# B_Main_board_v1_4.net
KiCad netlist of a schematic drawn in EAGLE
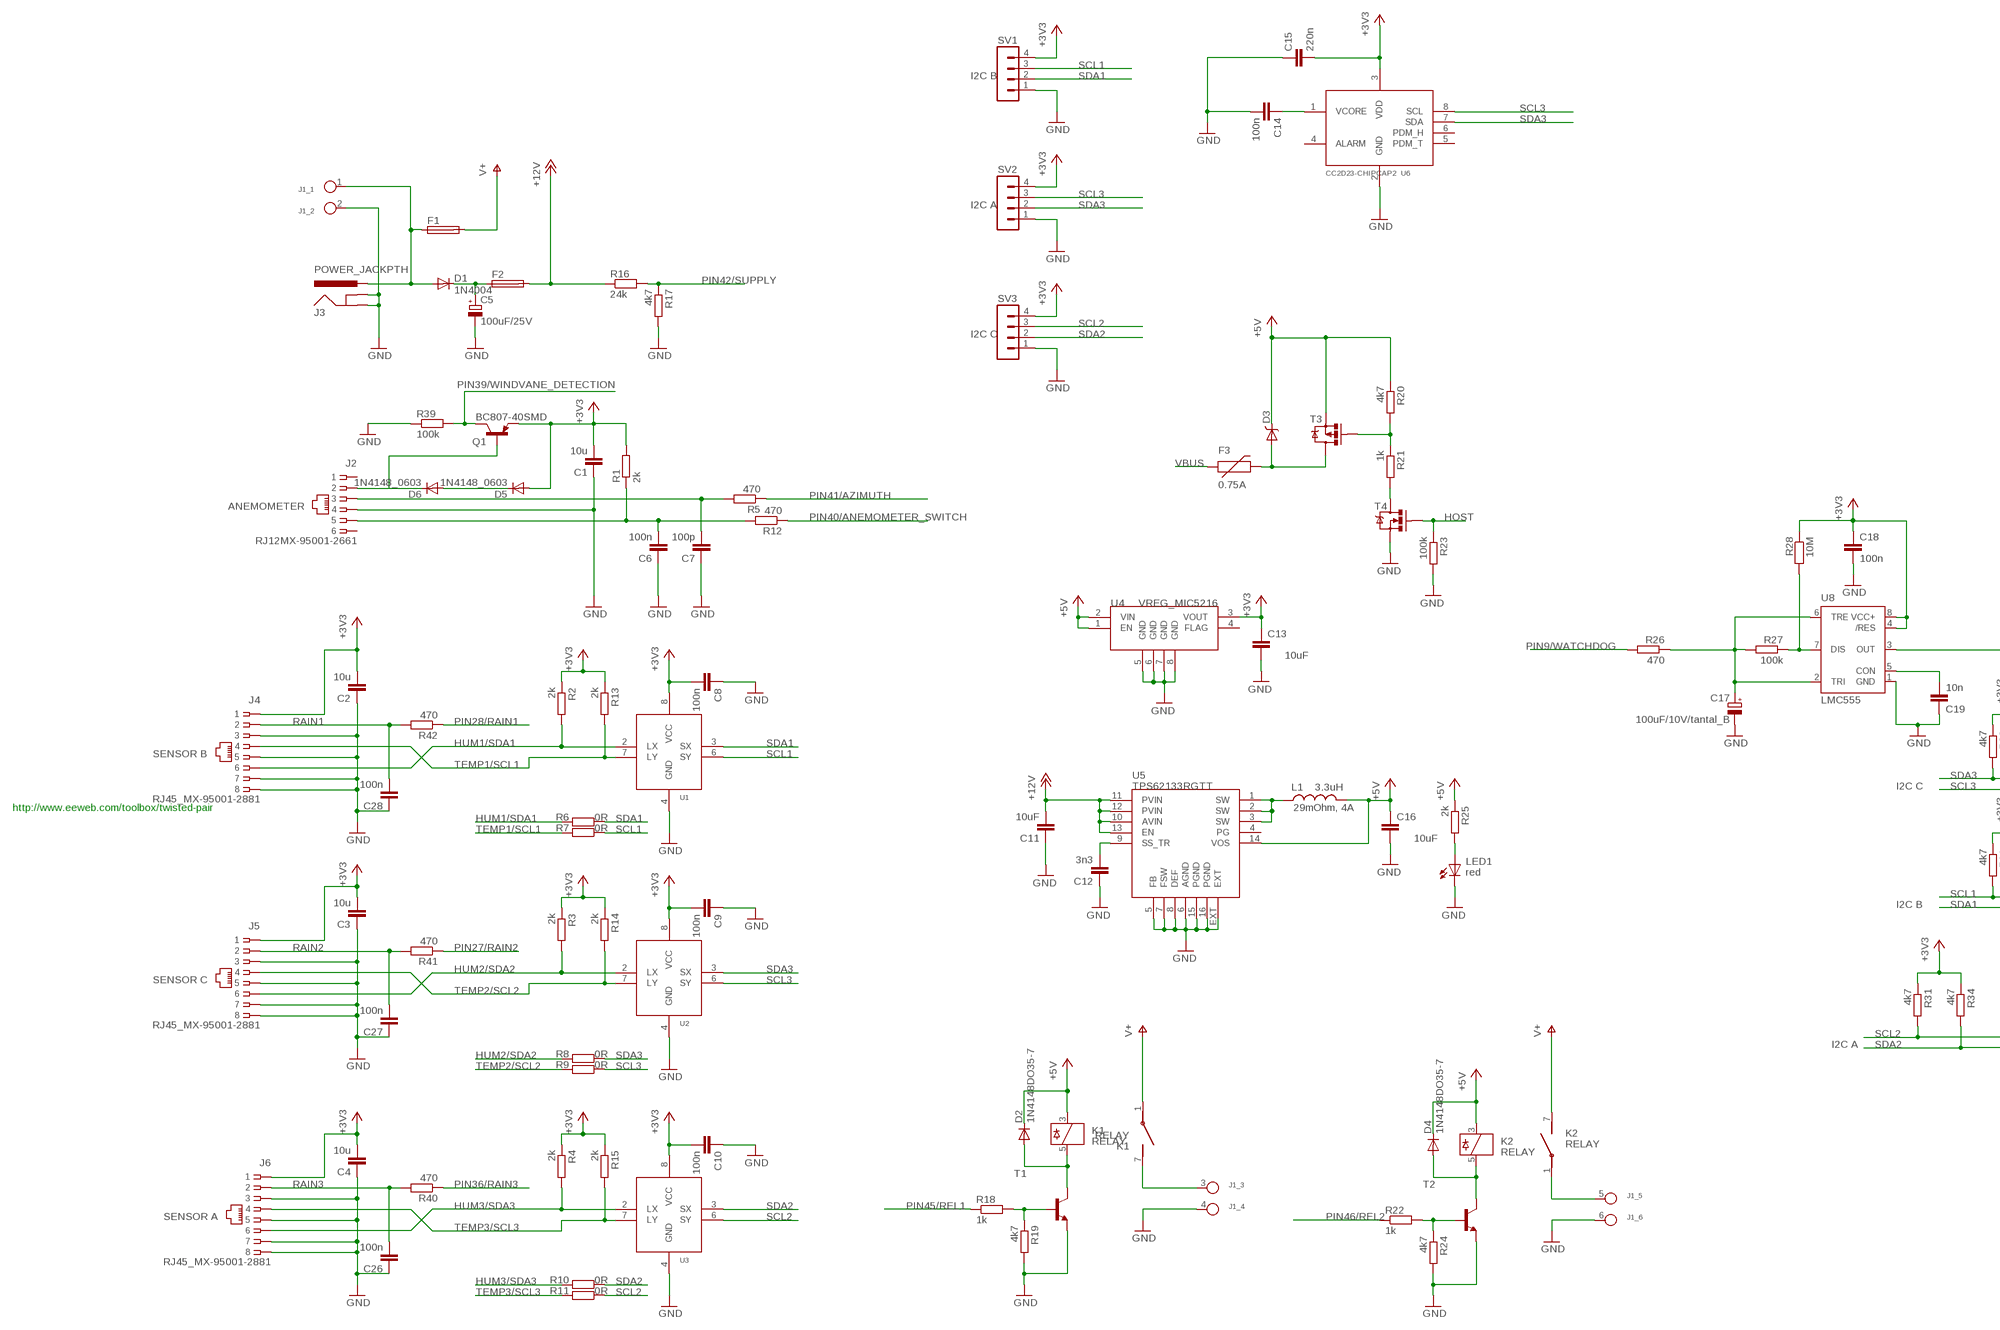
[diagram p0: schematic, sheet 1, part 1 of 2]
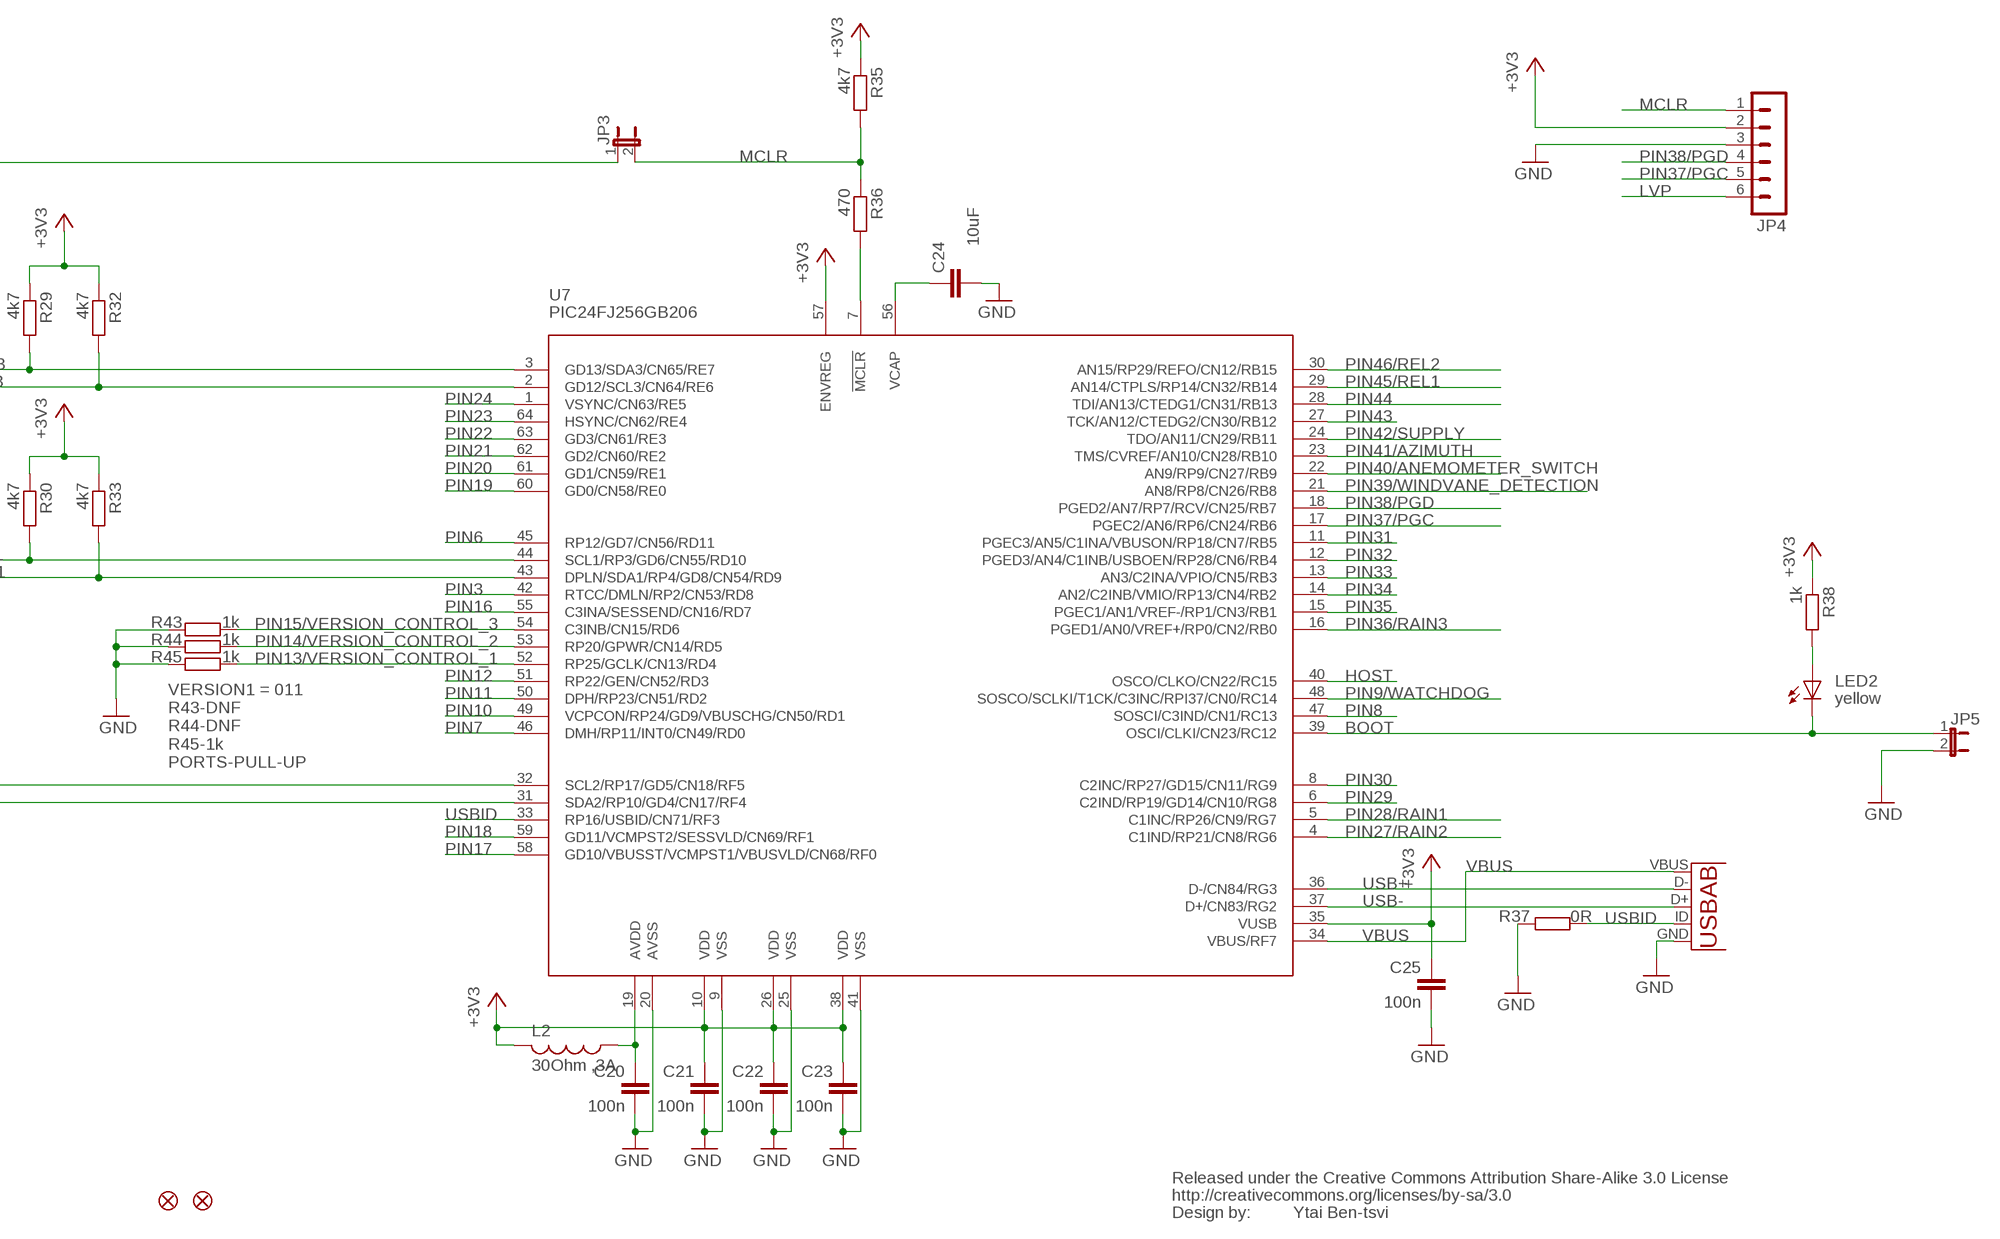
[diagram p1: schematic, sheet 1, part 2 of 2]

(export (version "E")
  (design (tool "Eeschema 10.0.6"))
  (components
    (comp (ref "C1")
      (value "10u")
      (footprint "eagle-import:C1206")
      (libsource (lib "eagle-import") (part "C-EUC1206"))
    )
    (comp (ref "C2")
      (value "10u")
      (footprint "eagle-import:C1206")
      (libsource (lib "eagle-import") (part "C-EUC1206"))
    )
    (comp (ref "C3")
      (value "10u")
      (footprint "eagle-import:C1206")
      (libsource (lib "eagle-import") (part "C-EUC1206"))
    )
    (comp (ref "C4")
      (value "10u")
      (footprint "eagle-import:C1206")
      (libsource (lib "eagle-import") (part "C-EUC1206"))
    )
    (comp (ref "C5")
      (value "100uF/25V")
      (footprint "eagle-import:E2-5")
      (libsource (lib "eagle-import") (part "CPOL-EUE2-5"))
    )
    (comp (ref "C6")
      (value "100n")
      (footprint "eagle-import:C1206")
      (libsource (lib "eagle-import") (part "C-EUC1206"))
    )
    (comp (ref "C7")
      (value "100p")
      (footprint "eagle-import:C1206")
      (libsource (lib "eagle-import") (part "C-EUC1206"))
    )
    (comp (ref "C8")
      (value "100n")
      (footprint "eagle-import:C1206")
      (libsource (lib "eagle-import") (part "C-EUC1206"))
    )
    (comp (ref "C9")
      (value "100n")
      (footprint "eagle-import:C1206")
      (libsource (lib "eagle-import") (part "C-EUC1206"))
    )
    (comp (ref "C10")
      (value "100n")
      (footprint "eagle-import:C1206")
      (libsource (lib "eagle-import") (part "C-EUC1206"))
    )
    (comp (ref "C11")
      (value "10uF")
      (footprint "eagle-import:C1206")
      (libsource (lib "eagle-import") (part "C-EUC1206"))
    )
    (comp (ref "C12")
      (value "3n3")
      (footprint "eagle-import:C1206")
      (libsource (lib "eagle-import") (part "C-EUC1206"))
    )
    (comp (ref "C13")
      (value "10uF")
      (footprint "eagle-import:C1206")
      (libsource (lib "eagle-import") (part "C-EUC1206"))
    )
    (comp (ref "C14")
      (value "100n")
      (footprint "eagle-import:C1206")
      (libsource (lib "eagle-import") (part "C-EUC1206"))
    )
    (comp (ref "C15")
      (value "220n")
      (footprint "eagle-import:C1206")
      (libsource (lib "eagle-import") (part "C-EUC1206"))
    )
    (comp (ref "C16")
      (value "10uF")
      (footprint "eagle-import:C1206")
      (libsource (lib "eagle-import") (part "C-EUC1206"))
    )
    (comp (ref "C17")
      (value "100uF/10V/tantal_B")
      (footprint "eagle-import:B_3528-21R")
      (libsource (lib "eagle-import") (part "rcl_CPOL-EUB/3528-21R"))
    )
    (comp (ref "C18")
      (value "100n")
      (footprint "eagle-import:C1206")
      (libsource (lib "eagle-import") (part "C-EUC1206"))
    )
    (comp (ref "C19")
      (value "10n")
      (footprint "eagle-import:C1206")
      (libsource (lib "eagle-import") (part "C-EUC1206"))
    )
    (comp (ref "C20")
      (value "100n")
      (footprint "eagle-import:C1206")
      (libsource (lib "eagle-import") (part "C-EUC1206"))
    )
    (comp (ref "C21")
      (value "100n")
      (footprint "eagle-import:C1206")
      (libsource (lib "eagle-import") (part "C-EUC1206"))
    )
    (comp (ref "C22")
      (value "100n")
      (footprint "eagle-import:C1206")
      (libsource (lib "eagle-import") (part "C-EUC1206"))
    )
    (comp (ref "C23")
      (value "100n")
      (footprint "eagle-import:C1206")
      (libsource (lib "eagle-import") (part "C-EUC1206"))
    )
    (comp (ref "C24")
      (value "10uF")
      (footprint "eagle-import:C1206")
      (libsource (lib "eagle-import") (part "C-EUC1206"))
    )
    (comp (ref "C25")
      (value "100n")
      (footprint "eagle-import:C1206")
      (libsource (lib "eagle-import") (part "C-EUC1206"))
    )
    (comp (ref "C26")
      (value "100n")
      (footprint "eagle-import:C1206")
      (libsource (lib "eagle-import") (part "C-EUC1206"))
    )
    (comp (ref "C27")
      (value "100n")
      (footprint "eagle-import:C1206")
      (libsource (lib "eagle-import") (part "C-EUC1206"))
    )
    (comp (ref "C28")
      (value "100n")
      (footprint "eagle-import:C1206")
      (libsource (lib "eagle-import") (part "C-EUC1206"))
    )
    (comp (ref "D1")
      (value "1N4004")
      (footprint "eagle-import:DO41-10")
      (libsource (lib "eagle-import") (part "1N4004"))
    )
    (comp (ref "D2")
      (value "1N4148DO35-7")
      (footprint "eagle-import:DO35-7")
      (libsource (lib "eagle-import") (part "1N4148DO35-7"))
    )
    (comp (ref "D3")
      (value "B340A")
      (footprint "eagle-import:SMA-DIODE")
      (fields (field (name "PART#") "B340A"))
      (libsource (lib "eagle-import") (part "DIODE-SCHOTTKY_"))
    )
    (comp (ref "D4")
      (value "1N4148DO35-7")
      (footprint "eagle-import:DO35-7")
      (libsource (lib "eagle-import") (part "1N4148DO35-7"))
    )
    (comp (ref "D5")
      (value "1N4148_0603")
      (footprint "eagle-import:D0603")
      (libsource (lib "eagle-import") (part "1N4148_0603"))
    )
    (comp (ref "D6")
      (value "1N4148_0603")
      (footprint "eagle-import:D0603")
      (libsource (lib "eagle-import") (part "1N4148_0603"))
    )
    (comp (ref "F1")
      (value "FUSE_HOLDER")
      (footprint "eagle-import:ZHL30")
      (libsource (lib "eagle-import") (part "FUSE_HOLDER"))
    )
    (comp (ref "F2")
      (value "FUSE_HOLDER")
      (footprint "eagle-import:ZHL30")
      (libsource (lib "eagle-import") (part "FUSE_HOLDER"))
    )
    (comp (ref "F3")
      (value "PTCSMD")
      (footprint "eagle-import:PTC-1206")
      (fields (field (name "PART#") "0ZCA0075FF2G"))
      (libsource (lib "eagle-import") (part "PTCSMD"))
    )
    (comp (ref "J1")
      (value "6P_CONN")
      (footprint "eagle-import:MOLEX_39543-0006")
      (libsource (lib "eagle-import") (part "6P_CONN"))
    )
    (comp (ref "J2")
      (value "RJ12MX-95001-2661")
      (footprint "eagle-import:MX-95001-2661")
      (libsource (lib "eagle-import") (part "RJ12MX-95001-2661"))
    )
    (comp (ref "J3")
      (value "POWER_JACKPTH")
      (footprint "eagle-import:PC-GK2.1")
      (libsource (lib "eagle-import") (part "POWER_JACKPTH"))
    )
    (comp (ref "J4")
      (value "RJ45_MX-95001-2881")
      (footprint "eagle-import:MX-95001-2881")
      (libsource (lib "eagle-import") (part "RJ45_MX-95001-2881"))
    )
    (comp (ref "J5")
      (value "RJ45_MX-95001-2881")
      (footprint "eagle-import:MX-95001-2881")
      (libsource (lib "eagle-import") (part "RJ45_MX-95001-2881"))
    )
    (comp (ref "J6")
      (value "RJ45_MX-95001-2881")
      (footprint "eagle-import:MX-95001-2881")
      (libsource (lib "eagle-import") (part "RJ45_MX-95001-2881"))
    )
    (comp (ref "J7")
      (value "10104111-0001LF")
      (footprint "eagle-import:USB-AB-MICRO-SMD")
      (libsource (lib "eagle-import") (part "USB_AB"))
    )
    (comp (ref "JP1")
      (value "FIDUCIALUFIDUCIAL")
      (footprint "eagle-import:MICRO-FIDUCIAL")
      (libsource (lib "eagle-import") (part "FIDUCIALUFIDUCIAL"))
    )
    (comp (ref "JP2")
      (value "FIDUCIALUFIDUCIAL")
      (footprint "eagle-import:MICRO-FIDUCIAL")
      (libsource (lib "eagle-import") (part "FIDUCIALUFIDUCIAL"))
    )
    (comp (ref "JP3")
      (value "JUMPER-2PTH")
      (footprint "eagle-import:1X02")
      (libsource (lib "eagle-import") (part "JUMPER-2PTH"))
    )
    (comp (ref "JP4")
      (value "MA06-1")
      (footprint "eagle-import:MA06-1")
      (libsource (lib "eagle-import") (part "MA06-1"))
    )
    (comp (ref "JP5")
      (value "JUMPER-2PTH")
      (footprint "eagle-import:1X02")
      (libsource (lib "eagle-import") (part "JUMPER-2PTH"))
    )
    (comp (ref "K1")
      (value "RELAY")
      (footprint "eagle-import:JV-5S-KT")
      (libsource (lib "eagle-import") (part "RELAY"))
    )
    (comp (ref "K2")
      (value "RELAY")
      (footprint "eagle-import:JV-5S-KT")
      (libsource (lib "eagle-import") (part "RELAY"))
    )
    (comp (ref "L1")
      (value "VLC5045T-3R3N")
      (footprint "eagle-import:CR54")
      (fields (field (name "AM") "3.3uH"))
      (libsource (lib "eagle-import") (part "INDUCTORCR54"))
    )
    (comp (ref "L2")
      (value "30Ohm ,3A")
      (footprint "eagle-import:R1206")
      (libsource (lib "eagle-import") (part "L-US"))
    )
    (comp (ref "LED1")
      (value "LS L29K-G1J2-1-Z")
      (footprint "eagle-import:LED-1206")
      (libsource (lib "eagle-import") (part "LED1206"))
    )
    (comp (ref "LED2")
      (value "LY L29K-J1K2-26-Z")
      (footprint "eagle-import:LED-1206")
      (libsource (lib "eagle-import") (part "LED1206"))
    )
    (comp (ref "Q1")
      (value "BC807-40SMD")
      (footprint "eagle-import:SOT23-BEC")
      (libsource (lib "eagle-import") (part "BC807SMD-40"))
    )
    (comp (ref "R1")
      (value "2k")
      (footprint "eagle-import:R1206")
      (libsource (lib "eagle-import") (part "R-EU_R1206"))
    )
    (comp (ref "R2")
      (value "2k")
      (footprint "eagle-import:R1206")
      (libsource (lib "eagle-import") (part "R-EU_R1206"))
    )
    (comp (ref "R3")
      (value "2k")
      (footprint "eagle-import:R1206")
      (libsource (lib "eagle-import") (part "R-EU_R1206"))
    )
    (comp (ref "R4")
      (value "2k")
      (footprint "eagle-import:R1206")
      (libsource (lib "eagle-import") (part "R-EU_R1206"))
    )
    (comp (ref "R5")
      (value "470")
      (footprint "eagle-import:R1206")
      (libsource (lib "eagle-import") (part "R-EU_R1206"))
    )
    (comp (ref "R6")
      (value "0R")
      (footprint "eagle-import:R1206")
      (libsource (lib "eagle-import") (part "R-EU_R1206"))
    )
    (comp (ref "R7")
      (value "0R")
      (footprint "eagle-import:R1206")
      (libsource (lib "eagle-import") (part "R-EU_R1206"))
    )
    (comp (ref "R8")
      (value "0R")
      (footprint "eagle-import:R1206")
      (libsource (lib "eagle-import") (part "R-EU_R1206"))
    )
    (comp (ref "R9")
      (value "0R")
      (footprint "eagle-import:R1206")
      (libsource (lib "eagle-import") (part "R-EU_R1206"))
    )
    (comp (ref "R10")
      (value "0R")
      (footprint "eagle-import:R1206")
      (libsource (lib "eagle-import") (part "R-EU_R1206"))
    )
    (comp (ref "R11")
      (value "0R")
      (footprint "eagle-import:R1206")
      (libsource (lib "eagle-import") (part "R-EU_R1206"))
    )
    (comp (ref "R12")
      (value "470")
      (footprint "eagle-import:R1206")
      (libsource (lib "eagle-import") (part "R-EU_R1206"))
    )
    (comp (ref "R13")
      (value "2k")
      (footprint "eagle-import:R1206")
      (libsource (lib "eagle-import") (part "R-EU_R1206"))
    )
    (comp (ref "R14")
      (value "2k")
      (footprint "eagle-import:R1206")
      (libsource (lib "eagle-import") (part "R-EU_R1206"))
    )
    (comp (ref "R15")
      (value "2k")
      (footprint "eagle-import:R1206")
      (libsource (lib "eagle-import") (part "R-EU_R1206"))
    )
    (comp (ref "R16")
      (value "24k")
      (footprint "eagle-import:R1206")
      (libsource (lib "eagle-import") (part "R-EU_R1206"))
    )
    (comp (ref "R17")
      (value "4k7")
      (footprint "eagle-import:R1206")
      (libsource (lib "eagle-import") (part "R-EU_R1206"))
    )
    (comp (ref "R18")
      (value "1k")
      (footprint "eagle-import:R1206")
      (libsource (lib "eagle-import") (part "R-EU_R1206"))
    )
    (comp (ref "R19")
      (value "4k7")
      (footprint "eagle-import:R1206")
      (libsource (lib "eagle-import") (part "R-EU_R1206"))
    )
    (comp (ref "R20")
      (value "4k7")
      (footprint "eagle-import:R1206")
      (libsource (lib "eagle-import") (part "R-EU_R1206"))
    )
    (comp (ref "R21")
      (value "1k")
      (footprint "eagle-import:R1206")
      (libsource (lib "eagle-import") (part "R-EU_R1206"))
    )
    (comp (ref "R22")
      (value "1k")
      (footprint "eagle-import:R1206")
      (libsource (lib "eagle-import") (part "R-EU_R1206"))
    )
    (comp (ref "R23")
      (value "100k")
      (footprint "eagle-import:R1206")
      (libsource (lib "eagle-import") (part "R-EU_R1206"))
    )
    (comp (ref "R24")
      (value "4k7")
      (footprint "eagle-import:R1206")
      (libsource (lib "eagle-import") (part "R-EU_R1206"))
    )
    (comp (ref "R25")
      (value "2k")
      (footprint "eagle-import:R1206")
      (libsource (lib "eagle-import") (part "R-EU_R1206"))
    )
    (comp (ref "R26")
      (value "470")
      (footprint "eagle-import:R1206")
      (libsource (lib "eagle-import") (part "R-EU_R1206"))
    )
    (comp (ref "R27")
      (value "100k")
      (footprint "eagle-import:R1206")
      (libsource (lib "eagle-import") (part "R-EU_R1206"))
    )
    (comp (ref "R28")
      (value "10M")
      (footprint "eagle-import:R1206")
      (libsource (lib "eagle-import") (part "R-EU_R1206"))
    )
    (comp (ref "R29")
      (value "4k7")
      (footprint "eagle-import:R1206")
      (libsource (lib "eagle-import") (part "R-EU_R1206"))
    )
    (comp (ref "R30")
      (value "4k7")
      (footprint "eagle-import:R1206")
      (libsource (lib "eagle-import") (part "R-EU_R1206"))
    )
    (comp (ref "R31")
      (value "4k7")
      (footprint "eagle-import:R1206")
      (libsource (lib "eagle-import") (part "R-EU_R1206"))
    )
    (comp (ref "R32")
      (value "4k7")
      (footprint "eagle-import:R1206")
      (libsource (lib "eagle-import") (part "R-EU_R1206"))
    )
    (comp (ref "R33")
      (value "4k7")
      (footprint "eagle-import:R1206")
      (libsource (lib "eagle-import") (part "R-EU_R1206"))
    )
    (comp (ref "R34")
      (value "4k7")
      (footprint "eagle-import:R1206")
      (libsource (lib "eagle-import") (part "R-EU_R1206"))
    )
    (comp (ref "R35")
      (value "4k7")
      (footprint "eagle-import:R1206")
      (libsource (lib "eagle-import") (part "R-EU_R1206"))
    )
    (comp (ref "R36")
      (value "470")
      (footprint "eagle-import:R1206")
      (libsource (lib "eagle-import") (part "R-EU_R1206"))
    )
    (comp (ref "R37")
      (value "0R")
      (footprint "eagle-import:R1206")
      (libsource (lib "eagle-import") (part "R-EU_R1206"))
    )
    (comp (ref "R38")
      (value "1k")
      (footprint "eagle-import:R1206")
      (libsource (lib "eagle-import") (part "R-EU_R1206"))
    )
    (comp (ref "R39")
      (value "100k")
      (footprint "eagle-import:R1206")
      (libsource (lib "eagle-import") (part "R-EU_R1206"))
    )
    (comp (ref "R40")
      (value "470")
      (footprint "eagle-import:R1206")
      (libsource (lib "eagle-import") (part "R-EU_R1206"))
    )
    (comp (ref "R41")
      (value "470")
      (footprint "eagle-import:R1206")
      (libsource (lib "eagle-import") (part "R-EU_R1206"))
    )
    (comp (ref "R42")
      (value "470")
      (footprint "eagle-import:R1206")
      (libsource (lib "eagle-import") (part "R-EU_R1206"))
    )
    (comp (ref "R43")
      (value "1k")
      (footprint "eagle-import:R1206")
      (libsource (lib "eagle-import") (part "R-EU_R1206"))
    )
    (comp (ref "R44")
      (value "1k")
      (footprint "eagle-import:R1206")
      (libsource (lib "eagle-import") (part "R-EU_R1206"))
    )
    (comp (ref "R45")
      (value "1k")
      (footprint "eagle-import:R1206")
      (libsource (lib "eagle-import") (part "R-EU_R1206"))
    )
    (comp (ref "SV1")
      (value "MA04-1")
      (footprint "eagle-import:MA04-1")
      (libsource (lib "eagle-import") (part "MA04-1"))
    )
    (comp (ref "SV2")
      (value "MA04-1")
      (footprint "eagle-import:MA04-1")
      (libsource (lib "eagle-import") (part "MA04-1"))
    )
    (comp (ref "SV3")
      (value "MA04-1")
      (footprint "eagle-import:MA04-1")
      (libsource (lib "eagle-import") (part "MA04-1"))
    )
    (comp (ref "T1")
      (value "BC817-16-NPN-SOT23-BEC")
      (footprint "eagle-import:SOT23-BEC")
      (libsource (lib "eagle-import") (part "-NPN-SOT23-BECBC817-16"))
    )
    (comp (ref "T2")
      (value "BC817-16-NPN-SOT23-BEC")
      (footprint "eagle-import:SOT23-BEC")
      (libsource (lib "eagle-import") (part "-NPN-SOT23-BECBC817-16"))
    )
    (comp (ref "T3")
      (value "IRLML2244")
      (footprint "eagle-import:SOT23-3")
      (libsource (lib "eagle-import") (part "MOSFET-PCHANNELSMD"))
    )
    (comp (ref "T4")
      (value "2N7002PW")
      (footprint "eagle-import:SOT323")
      (fields (field (name "PART#") "2N7002PW"))
      (libsource (lib "eagle-import") (part "MOSFET-NCHANNELSOT323"))
    )
    (comp (ref "U$1")
      (value "CREATIVE_COMMONS")
      (footprint "eagle-import:CREATIVE_COMMONS")
      (libsource (lib "eagle-import") (part "CREATIVE_COMMONS"))
    )
    (comp (ref "U1")
      (value "P82B715_I2C_BUS_EXTENDER")
      (footprint "eagle-import:SO-08")
      (libsource (lib "eagle-import") (part "P82B715_I2C_BUS_EXTENDER"))
    )
    (comp (ref "U2")
      (value "P82B715_I2C_BUS_EXTENDER")
      (footprint "eagle-import:SO-08")
      (libsource (lib "eagle-import") (part "P82B715_I2C_BUS_EXTENDER"))
    )
    (comp (ref "U3")
      (value "P82B715_I2C_BUS_EXTENDER")
      (footprint "eagle-import:SO-08")
      (libsource (lib "eagle-import") (part "P82B715_I2C_BUS_EXTENDER"))
    )
    (comp (ref "U4")
      (value "VREG_MIC5216")
      (footprint "eagle-import:MSOP8")
      (libsource (lib "eagle-import") (part "VREG_MIC5216"))
    )
    (comp (ref "U5")
      (value "TPS62133RGTT")
      (footprint "eagle-import:QFN16-3X3MM")
      (libsource (lib "eagle-import") (part "TPS6214X"))
    )
    (comp (ref "U6")
      (value "CC2D23-CHIPCAP2")
      (footprint "eagle-import:CC2D23-CHIPCAP2")
      (libsource (lib "eagle-import") (part "CC2D23-CHIPCAP2"))
    )
    (comp (ref "U7")
      (value "PIC24FJ256GB206")
      (footprint "eagle-import:PIC24FXXX_TQFP64")
      (libsource (lib "eagle-import") (part "PIC24FXXXDAX06"))
    )
    (comp (ref "U8")
      (value "LMC555")
      (footprint "eagle-import:SO08")
      (libsource (lib "eagle-import") (part "NE555D"))
    )
  )
  (nets
    (net (code "1") (name "+3V3") (class "Default")
      (node (ref "C1") (pin "2") (pinfunction "2_2") (pintype "passive"))
      (node (ref "C10") (pin "2") (pinfunction "2_2") (pintype "passive"))
      (node (ref "C13") (pin "2") (pinfunction "2_2") (pintype "passive"))
      (node (ref "C15") (pin "2") (pinfunction "2_2") (pintype "passive"))
      (node (ref "C18") (pin "1") (pinfunction "1_1") (pintype "passive"))
      (node (ref "C2") (pin "2") (pinfunction "2_2") (pintype "passive"))
      (node (ref "C21") (pin "1") (pinfunction "1_1") (pintype "passive"))
      (node (ref "C22") (pin "1") (pinfunction "1_1") (pintype "passive"))
      (node (ref "C23") (pin "1") (pinfunction "1_1") (pintype "passive"))
      (node (ref "C25") (pin "1") (pinfunction "1_1") (pintype "passive"))
      (node (ref "C3") (pin "2") (pinfunction "2_2") (pintype "passive"))
      (node (ref "C4") (pin "2") (pinfunction "2_2") (pintype "passive"))
      (node (ref "C8") (pin "2") (pinfunction "2_2") (pintype "passive"))
      (node (ref "C9") (pin "2") (pinfunction "2_2") (pintype "passive"))
      (node (ref "D5") (pin "A") (pinfunction "A_A") (pintype "passive"))
      (node (ref "J4") (pin "1") (pinfunction "1_1") (pintype "passive"))
      (node (ref "J5") (pin "1") (pinfunction "1_1") (pintype "passive"))
      (node (ref "J6") (pin "1") (pinfunction "1_1") (pintype "passive"))
      (node (ref "JP4") (pin "2") (pinfunction "2_2") (pintype "passive"))
      (node (ref "L2") (pin "2") (pinfunction "2_2") (pintype "passive"))
      (node (ref "Q1") (pin "E") (pinfunction "E_E") (pintype "passive"))
      (node (ref "R1") (pin "2") (pinfunction "2_2") (pintype "passive"))
      (node (ref "R13") (pin "1") (pinfunction "1_1") (pintype "passive"))
      (node (ref "R14") (pin "1") (pinfunction "1_1") (pintype "passive"))
      (node (ref "R15") (pin "1") (pinfunction "1_1") (pintype "passive"))
      (node (ref "R2") (pin "1") (pinfunction "1_1") (pintype "passive"))
      (node (ref "R28") (pin "1") (pinfunction "1_1") (pintype "passive"))
      (node (ref "R29") (pin "1") (pinfunction "1_1") (pintype "passive"))
      (node (ref "R3") (pin "1") (pinfunction "1_1") (pintype "passive"))
      (node (ref "R30") (pin "1") (pinfunction "1_1") (pintype "passive"))
      (node (ref "R31") (pin "1") (pinfunction "1_1") (pintype "passive"))
      (node (ref "R32") (pin "1") (pinfunction "1_1") (pintype "passive"))
      (node (ref "R33") (pin "1") (pinfunction "1_1") (pintype "passive"))
      (node (ref "R34") (pin "1") (pinfunction "1_1") (pintype "passive"))
      (node (ref "R35") (pin "1") (pinfunction "1_1") (pintype "passive"))
      (node (ref "R38") (pin "1") (pinfunction "1_1") (pintype "passive"))
      (node (ref "R4") (pin "1") (pinfunction "1_1") (pintype "passive"))
      (node (ref "SV1") (pin "4") (pinfunction "4_4") (pintype "passive"))
      (node (ref "SV2") (pin "4") (pinfunction "4_4") (pintype "passive"))
      (node (ref "SV3") (pin "4") (pinfunction "4_4") (pintype "passive"))
      (node (ref "U1") (pin "8") (pinfunction "VCC_8") (pintype "bidirectional"))
      (node (ref "U2") (pin "8") (pinfunction "VCC_8") (pintype "bidirectional"))
      (node (ref "U3") (pin "8") (pinfunction "VCC_8") (pintype "bidirectional"))
      (node (ref "U4") (pin "3") (pinfunction "VOUT_3") (pintype "bidirectional"))
      (node (ref "U6") (pin "3") (pinfunction "VDD_3") (pintype "bidirectional"))
      (node (ref "U7") (pin "10") (pinfunction "VDD_10") (pintype "power_in"))
      (node (ref "U7") (pin "26") (pinfunction "VDD_26") (pintype "power_in"))
      (node (ref "U7") (pin "35") (pinfunction "VUSB_35") (pintype "power_in"))
      (node (ref "U7") (pin "38") (pinfunction "VDD_38") (pintype "power_in"))
      (node (ref "U7") (pin "57") (pinfunction "ENVREG_57") (pintype "input"))
      (node (ref "U8") (pin "4") (pinfunction "/RES_4") (pintype "input"))
      (node (ref "U8") (pin "8") (pinfunction "VCC+_8") (pintype "power_in"))
    )
    (net (code "2") (name "+5V") (class "Default")
      (node (ref "C16") (pin "2") (pinfunction "2_2") (pintype "passive"))
      (node (ref "D2") (pin "C") (pinfunction "C_C") (pintype "passive"))
      (node (ref "D3") (pin "C") (pinfunction "C_C") (pintype "passive"))
      (node (ref "D4") (pin "C") (pinfunction "C_C") (pintype "passive"))
      (node (ref "K1") (pin "3") (pinfunction "3_3") (pintype "passive"))
      (node (ref "K2") (pin "3") (pinfunction "3_3") (pintype "passive"))
      (node (ref "L1") (pin "P$2") (pinfunction "2_P$2") (pintype "passive"))
      (node (ref "R20") (pin "1") (pinfunction "1_1") (pintype "passive"))
      (node (ref "R25") (pin "1") (pinfunction "1_1") (pintype "passive"))
      (node (ref "T3") (pin "2") (pinfunction "S_2") (pintype "passive"))
      (node (ref "U4") (pin "1") (pinfunction "EN_1") (pintype "bidirectional"))
      (node (ref "U4") (pin "2") (pinfunction "VIN_2") (pintype "bidirectional"))
      (node (ref "U5") (pin "14") (pinfunction "VOS_14") (pintype "bidirectional"))
    )
    (net (code "3") (name "+12V") (class "Default")
      (node (ref "C11") (pin "2") (pinfunction "2_2") (pintype "passive"))
      (node (ref "F2") (pin "2") (pinfunction "2_2") (pintype "passive"))
      (node (ref "R16") (pin "1") (pinfunction "1_1") (pintype "passive"))
      (node (ref "U5") (pin "10") (pinfunction "AVIN_10") (pintype "bidirectional"))
      (node (ref "U5") (pin "11") (pinfunction "PVIN_11") (pintype "bidirectional"))
      (node (ref "U5") (pin "12") (pinfunction "PVIN_12") (pintype "bidirectional"))
      (node (ref "U5") (pin "13") (pinfunction "EN_13") (pintype "bidirectional"))
    )
    (net (code "4") (name "/BOOT") (class "Default")
      (node (ref "JP5") (pin "1") (pinfunction "1_1") (pintype "passive"))
      (node (ref "LED2") (pin "C") (pinfunction "C_C") (pintype "passive"))
      (node (ref "U7") (pin "39") (pinfunction "OSCI/CLKI/CN23/RC12_39") (pintype "bidirectional"))
    )
    (net (code "5") (name "/HOST") (class "Default")
      (node (ref "R23") (pin "1") (pinfunction "1_1") (pintype "passive"))
      (node (ref "T4") (pin "1") (pinfunction "G_1") (pintype "passive"))
      (node (ref "U7") (pin "40") (pinfunction "OSCO/CLKO/CN22/RC15_40") (pintype "bidirectional"))
    )
    (net (code "6") (name "/HUM1{slash}SDA1") (class "Default")
      (node (ref "J4") (pin "6") (pinfunction "6_6") (pintype "passive"))
      (node (ref "R2") (pin "2") (pinfunction "2_2") (pintype "passive"))
      (node (ref "R6") (pin "2") (pinfunction "2_2") (pintype "passive"))
      (node (ref "U1") (pin "2") (pinfunction "LX_2") (pintype "bidirectional"))
    )
    (net (code "7") (name "/HUM2{slash}SDA2") (class "Default")
      (node (ref "J5") (pin "6") (pinfunction "6_6") (pintype "passive"))
      (node (ref "R3") (pin "2") (pinfunction "2_2") (pintype "passive"))
      (node (ref "R8") (pin "2") (pinfunction "2_2") (pintype "passive"))
      (node (ref "U2") (pin "2") (pinfunction "LX_2") (pintype "bidirectional"))
    )
    (net (code "8") (name "/HUM3{slash}SDA3") (class "Default")
      (node (ref "J6") (pin "6") (pinfunction "6_6") (pintype "passive"))
      (node (ref "R10") (pin "2") (pinfunction "2_2") (pintype "passive"))
      (node (ref "R4") (pin "2") (pinfunction "2_2") (pintype "passive"))
      (node (ref "U3") (pin "2") (pinfunction "LX_2") (pintype "bidirectional"))
    )
    (net (code "9") (name "/LVP") (class "Default")
      (node (ref "JP4") (pin "6") (pinfunction "6_6") (pintype "passive"))
    )
    (net (code "10") (name "/MCLR") (class "Default")
      (node (ref "JP3") (pin "2") (pinfunction "2_2") (pintype "passive"))
      (node (ref "JP4") (pin "1") (pinfunction "1_1") (pintype "passive"))
      (node (ref "R35") (pin "2") (pinfunction "2_2") (pintype "passive"))
      (node (ref "R36") (pin "1") (pinfunction "1_1") (pintype "passive"))
    )
    (net (code "11") (name "/PIN3") (class "Default")
      (node (ref "U7") (pin "42") (pinfunction "RTCC/DMLN/RP2/CN53/RD8_42") (pintype "bidirectional"))
    )
    (net (code "12") (name "/PIN6") (class "Default")
      (node (ref "U7") (pin "45") (pinfunction "RP12/GD7/CN56/RD11_45") (pintype "bidirectional"))
    )
    (net (code "13") (name "/PIN7") (class "Default")
      (node (ref "U7") (pin "46") (pinfunction "DMH/RP11/INT0/CN49/RD0_46") (pintype "bidirectional"))
    )
    (net (code "14") (name "/PIN8") (class "Default")
      (node (ref "U7") (pin "47") (pinfunction "SOSCI/C3IND/CN1/RC13_47") (pintype "bidirectional"))
    )
    (net (code "15") (name "/PIN9{slash}WATCHDOG") (class "Default")
      (node (ref "R26") (pin "2") (pinfunction "2_2") (pintype "passive"))
      (node (ref "U7") (pin "48") (pinfunction "SOSCO/SCLKI/T1CK/C3INC/RPI37/CN0/RC14_48") (pintype "bidirectional"))
    )
    (net (code "16") (name "/PIN10") (class "Default")
      (node (ref "U7") (pin "49") (pinfunction "VCPCON/RP24/GD9/VBUSCHG/CN50/RD1_49") (pintype "bidirectional"))
    )
    (net (code "17") (name "/PIN11") (class "Default")
      (node (ref "U7") (pin "50") (pinfunction "DPH/RP23/CN51/RD2_50") (pintype "bidirectional"))
    )
    (net (code "18") (name "/PIN12") (class "Default")
      (node (ref "U7") (pin "51") (pinfunction "RP22/GEN/CN52/RD3_51") (pintype "bidirectional"))
    )
    (net (code "19") (name "/PIN13{slash}VERSION_CONTROL_1") (class "Default")
      (node (ref "R45") (pin "2") (pinfunction "2_2") (pintype "passive"))
      (node (ref "U7") (pin "52") (pinfunction "RP25/GCLK/CN13/RD4_52") (pintype "bidirectional"))
    )
    (net (code "20") (name "/PIN14{slash}VERSION_CONTROL_2") (class "Default")
      (node (ref "R44") (pin "2") (pinfunction "2_2") (pintype "passive"))
      (node (ref "U7") (pin "53") (pinfunction "RP20/GPWR/CN14/RD5_53") (pintype "bidirectional"))
    )
    (net (code "21") (name "/PIN15{slash}VERSION_CONTROL_3") (class "Default")
      (node (ref "R43") (pin "2") (pinfunction "2_2") (pintype "passive"))
      (node (ref "U7") (pin "54") (pinfunction "C3INB/CN15/RD6_54") (pintype "bidirectional"))
    )
    (net (code "22") (name "/PIN16") (class "Default")
      (node (ref "U7") (pin "55") (pinfunction "C3INA/SESSEND/CN16/RD7_55") (pintype "bidirectional"))
    )
    (net (code "23") (name "/PIN17") (class "Default")
      (node (ref "U7") (pin "58") (pinfunction "GD10/VBUSST/VCMPST1/VBUSVLD/CN68/RF0_58") (pintype "bidirectional"))
    )
    (net (code "24") (name "/PIN18") (class "Default")
      (node (ref "U7") (pin "59") (pinfunction "GD11/VCMPST2/SESSVLD/CN69/RF1_59") (pintype "bidirectional"))
    )
    (net (code "25") (name "/PIN19") (class "Default")
      (node (ref "U7") (pin "60") (pinfunction "GD0/CN58/RE0_60") (pintype "bidirectional"))
    )
    (net (code "26") (name "/PIN20") (class "Default")
      (node (ref "U7") (pin "61") (pinfunction "GD1/CN59/RE1_61") (pintype "bidirectional"))
    )
    (net (code "27") (name "/PIN21") (class "Default")
      (node (ref "U7") (pin "62") (pinfunction "GD2/CN60/RE2_62") (pintype "bidirectional"))
    )
    (net (code "28") (name "/PIN22") (class "Default")
      (node (ref "U7") (pin "63") (pinfunction "GD3/CN61/RE3_63") (pintype "bidirectional"))
    )
    (net (code "29") (name "/PIN23") (class "Default")
      (node (ref "U7") (pin "64") (pinfunction "HSYNC/CN62/RE4_64") (pintype "bidirectional"))
    )
    (net (code "30") (name "/PIN24") (class "Default")
      (node (ref "U7") (pin "1") (pinfunction "VSYNC/CN63/RE5_1") (pintype "bidirectional"))
    )
    (net (code "31") (name "/PIN27{slash}RAIN2") (class "Default")
      (node (ref "R41") (pin "1") (pinfunction "1_1") (pintype "passive"))
      (node (ref "U7") (pin "4") (pinfunction "C1IND/RP21/CN8/RG6_4") (pintype "bidirectional"))
    )
    (net (code "32") (name "/PIN28{slash}RAIN1") (class "Default")
      (node (ref "R42") (pin "1") (pinfunction "1_1") (pintype "passive"))
      (node (ref "U7") (pin "5") (pinfunction "C1INC/RP26/CN9/RG7_5") (pintype "bidirectional"))
    )
    (net (code "33") (name "/PIN29") (class "Default")
      (node (ref "U7") (pin "6") (pinfunction "C2IND/RP19/GD14/CN10/RG8_6") (pintype "bidirectional"))
    )
    (net (code "34") (name "/PIN30") (class "Default")
      (node (ref "U7") (pin "8") (pinfunction "C2INC/RP27/GD15/CN11/RG9_8") (pintype "bidirectional"))
    )
    (net (code "35") (name "/PIN31") (class "Default")
      (node (ref "U7") (pin "11") (pinfunction "PGEC3/AN5/C1INA/VBUSON/RP18/CN7/RB5_11") (pintype "bidirectional"))
    )
    (net (code "36") (name "/PIN32") (class "Default")
      (node (ref "U7") (pin "12") (pinfunction "PGED3/AN4/C1INB/USBOEN/RP28/CN6/RB4_12") (pintype "bidirectional"))
    )
    (net (code "37") (name "/PIN33") (class "Default")
      (node (ref "U7") (pin "13") (pinfunction "AN3/C2INA/VPIO/CN5/RB3_13") (pintype "bidirectional"))
    )
    (net (code "38") (name "/PIN34") (class "Default")
      (node (ref "U7") (pin "14") (pinfunction "AN2/C2INB/VMIO/RP13/CN4/RB2_14") (pintype "bidirectional"))
    )
    (net (code "39") (name "/PIN35") (class "Default")
      (node (ref "U7") (pin "15") (pinfunction "PGEC1/AN1/VREF-/RP1/CN3/RB1_15") (pintype "bidirectional"))
    )
    (net (code "40") (name "/PIN36{slash}RAIN3") (class "Default")
      (node (ref "R40") (pin "1") (pinfunction "1_1") (pintype "passive"))
      (node (ref "U7") (pin "16") (pinfunction "PGED1/AN0/VREF+/RP0/CN2/RB0_16") (pintype "bidirectional"))
    )
    (net (code "41") (name "/PIN37{slash}PGC") (class "Default")
      (node (ref "JP4") (pin "5") (pinfunction "5_5") (pintype "passive"))
      (node (ref "U7") (pin "17") (pinfunction "PGEC2/AN6/RP6/CN24/RB6_17") (pintype "bidirectional"))
    )
    (net (code "42") (name "/PIN38{slash}PGD") (class "Default")
      (node (ref "JP4") (pin "4") (pinfunction "4_4") (pintype "passive"))
      (node (ref "U7") (pin "18") (pinfunction "PGED2/AN7/RP7/RCV/CN25/RB7_18") (pintype "bidirectional"))
    )
    (net (code "43") (name "/PIN39{slash}WINDVANE_DETECTION") (class "Default")
      (node (ref "Q1") (pin "C") (pinfunction "C_C") (pintype "passive"))
      (node (ref "R39") (pin "2") (pinfunction "2_2") (pintype "passive"))
      (node (ref "U7") (pin "21") (pinfunction "AN8/RP8/CN26/RB8_21") (pintype "bidirectional"))
    )
    (net (code "44") (name "/PIN40{slash}ANEMOMETER_SWITCH") (class "Default")
      (node (ref "R12") (pin "1") (pinfunction "1_1") (pintype "passive"))
      (node (ref "U7") (pin "22") (pinfunction "AN9/RP9/CN27/RB9_22") (pintype "bidirectional"))
    )
    (net (code "45") (name "/PIN41{slash}AZIMUTH") (class "Default")
      (node (ref "R5") (pin "1") (pinfunction "1_1") (pintype "passive"))
      (node (ref "U7") (pin "23") (pinfunction "TMS/CVREF/AN10/CN28/RB10_23") (pintype "bidirectional"))
    )
    (net (code "46") (name "/PIN42{slash}SUPPLY") (class "Default")
      (node (ref "R16") (pin "2") (pinfunction "2_2") (pintype "passive"))
      (node (ref "R17") (pin "1") (pinfunction "1_1") (pintype "passive"))
      (node (ref "U7") (pin "24") (pinfunction "TDO/AN11/CN29/RB11_24") (pintype "bidirectional"))
    )
    (net (code "47") (name "/PIN43") (class "Default")
      (node (ref "U7") (pin "27") (pinfunction "TCK/AN12/CTEDG2/CN30/RB12_27") (pintype "bidirectional"))
    )
    (net (code "48") (name "/PIN44") (class "Default")
      (node (ref "U7") (pin "28") (pinfunction "TDI/AN13/CTEDG1/CN31/RB13_28") (pintype "bidirectional"))
    )
    (net (code "49") (name "/PIN45{slash}REL1") (class "Default")
      (node (ref "R18") (pin "1") (pinfunction "1_1") (pintype "passive"))
      (node (ref "U7") (pin "29") (pinfunction "AN14/CTPLS/RP14/CN32/RB14_29") (pintype "bidirectional"))
    )
    (net (code "50") (name "/PIN46{slash}REL2") (class "Default")
      (node (ref "R22") (pin "1") (pinfunction "1_1") (pintype "passive"))
      (node (ref "U7") (pin "30") (pinfunction "AN15/RP29/REFO/CN12/RB15_30") (pintype "bidirectional"))
    )
    (net (code "51") (name "/RAIN1") (class "Default")
      (node (ref "C28") (pin "2") (pinfunction "2_2") (pintype "passive"))
      (node (ref "J4") (pin "2") (pinfunction "2_2") (pintype "passive"))
      (node (ref "R42") (pin "2") (pinfunction "2_2") (pintype "passive"))
    )
    (net (code "52") (name "/RAIN2") (class "Default")
      (node (ref "C27") (pin "2") (pinfunction "2_2") (pintype "passive"))
      (node (ref "J5") (pin "2") (pinfunction "2_2") (pintype "passive"))
      (node (ref "R41") (pin "2") (pinfunction "2_2") (pintype "passive"))
    )
    (net (code "53") (name "/RAIN3") (class "Default")
      (node (ref "C26") (pin "2") (pinfunction "2_2") (pintype "passive"))
      (node (ref "J6") (pin "2") (pinfunction "2_2") (pintype "passive"))
      (node (ref "R40") (pin "2") (pinfunction "2_2") (pintype "passive"))
    )
    (net (code "54") (name "/SCL1") (class "Default")
      (node (ref "R30") (pin "2") (pinfunction "2_2") (pintype "passive"))
      (node (ref "R7") (pin "1") (pinfunction "1_1") (pintype "passive"))
      (node (ref "SV1") (pin "3") (pinfunction "3_3") (pintype "passive"))
      (node (ref "U1") (pin "6") (pinfunction "SY_6") (pintype "bidirectional"))
      (node (ref "U7") (pin "44") (pinfunction "SCL1/RP3/GD6/CN55/RD10_44") (pintype "bidirectional"))
    )
    (net (code "55") (name "/SCL2") (class "Default")
      (node (ref "R11") (pin "1") (pinfunction "1_1") (pintype "passive"))
      (node (ref "R31") (pin "2") (pinfunction "2_2") (pintype "passive"))
      (node (ref "SV3") (pin "3") (pinfunction "3_3") (pintype "passive"))
      (node (ref "U3") (pin "6") (pinfunction "SY_6") (pintype "bidirectional"))
      (node (ref "U7") (pin "32") (pinfunction "SCL2/RP17/GD5/CN18/RF5_32") (pintype "bidirectional"))
    )
    (net (code "56") (name "/SCL3") (class "Default")
      (node (ref "R32") (pin "2") (pinfunction "2_2") (pintype "passive"))
      (node (ref "R9") (pin "1") (pinfunction "1_1") (pintype "passive"))
      (node (ref "SV2") (pin "3") (pinfunction "3_3") (pintype "passive"))
      (node (ref "U2") (pin "6") (pinfunction "SY_6") (pintype "bidirectional"))
      (node (ref "U6") (pin "8") (pinfunction "SCL_8") (pintype "bidirectional"))
      (node (ref "U7") (pin "2") (pinfunction "GD12/SCL3/CN64/RE6_2") (pintype "bidirectional"))
    )
    (net (code "57") (name "/SDA1") (class "Default")
      (node (ref "R33") (pin "2") (pinfunction "2_2") (pintype "passive"))
      (node (ref "R6") (pin "1") (pinfunction "1_1") (pintype "passive"))
      (node (ref "SV1") (pin "2") (pinfunction "2_2") (pintype "passive"))
      (node (ref "U1") (pin "3") (pinfunction "SX_3") (pintype "bidirectional"))
      (node (ref "U7") (pin "43") (pinfunction "DPLN/SDA1/RP4/GD8/CN54/RD9_43") (pintype "bidirectional"))
    )
    (net (code "58") (name "/SDA2") (class "Default")
      (node (ref "R10") (pin "1") (pinfunction "1_1") (pintype "passive"))
      (node (ref "R34") (pin "2") (pinfunction "2_2") (pintype "passive"))
      (node (ref "SV3") (pin "2") (pinfunction "2_2") (pintype "passive"))
      (node (ref "U3") (pin "3") (pinfunction "SX_3") (pintype "bidirectional"))
      (node (ref "U7") (pin "31") (pinfunction "SDA2/RP10/GD4/CN17/RF4_31") (pintype "bidirectional"))
    )
    (net (code "59") (name "/SDA3") (class "Default")
      (node (ref "R29") (pin "2") (pinfunction "2_2") (pintype "passive"))
      (node (ref "R8") (pin "1") (pinfunction "1_1") (pintype "passive"))
      (node (ref "SV2") (pin "2") (pinfunction "2_2") (pintype "passive"))
      (node (ref "U2") (pin "3") (pinfunction "SX_3") (pintype "bidirectional"))
      (node (ref "U6") (pin "7") (pinfunction "SDA_7") (pintype "bidirectional"))
      (node (ref "U7") (pin "3") (pinfunction "GD13/SDA3/CN65/RE7_3") (pintype "bidirectional"))
    )
    (net (code "60") (name "/TEMP1{slash}SCL1") (class "Default")
      (node (ref "J4") (pin "4") (pinfunction "4_4") (pintype "passive"))
      (node (ref "R13") (pin "2") (pinfunction "2_2") (pintype "passive"))
      (node (ref "R7") (pin "2") (pinfunction "2_2") (pintype "passive"))
      (node (ref "U1") (pin "7") (pinfunction "LY_7") (pintype "bidirectional"))
    )
    (net (code "61") (name "/TEMP2{slash}SCL2") (class "Default")
      (node (ref "J5") (pin "4") (pinfunction "4_4") (pintype "passive"))
      (node (ref "R14") (pin "2") (pinfunction "2_2") (pintype "passive"))
      (node (ref "R9") (pin "2") (pinfunction "2_2") (pintype "passive"))
      (node (ref "U2") (pin "7") (pinfunction "LY_7") (pintype "bidirectional"))
    )
    (net (code "62") (name "/TEMP3{slash}SCL3") (class "Default")
      (node (ref "J6") (pin "4") (pinfunction "4_4") (pintype "passive"))
      (node (ref "R11") (pin "2") (pinfunction "2_2") (pintype "passive"))
      (node (ref "R15") (pin "2") (pinfunction "2_2") (pintype "passive"))
      (node (ref "U3") (pin "7") (pinfunction "LY_7") (pintype "bidirectional"))
    )
    (net (code "63") (name "/USB+") (class "Default")
      (node (ref "J7") (pin "D-") (pinfunction "D-_D-") (pintype "bidirectional"))
      (node (ref "U7") (pin "36") (pinfunction "D-/CN84/RG3_36") (pintype "bidirectional"))
    )
    (net (code "64") (name "/USB-") (class "Default")
      (node (ref "J7") (pin "D+") (pinfunction "D+_D+") (pintype "bidirectional"))
      (node (ref "U7") (pin "37") (pinfunction "D+/CN83/RG2_37") (pintype "bidirectional"))
    )
    (net (code "65") (name "/USBID") (class "Default")
      (node (ref "J7") (pin "ID") (pinfunction "USBID_ID") (pintype "bidirectional"))
      (node (ref "R37") (pin "1") (pinfunction "1_1") (pintype "passive"))
      (node (ref "U7") (pin "33") (pinfunction "RP16/USBID/CN71/RF3_33") (pintype "bidirectional"))
    )
    (net (code "66") (name "/VBUS") (class "Default")
      (node (ref "F3") (pin "1") (pinfunction "1_1") (pintype "bidirectional"))
      (node (ref "J7") (pin "VBUS") (pinfunction "VBUS_VBUS") (pintype "bidirectional"))
      (node (ref "U7") (pin "34") (pinfunction "VBUS/RF7_34") (pintype "input"))
    )
    (net (code "67") (name "GND") (class "Default")
      (node (ref "C1") (pin "1") (pinfunction "1_1") (pintype "passive"))
      (node (ref "C10") (pin "1") (pinfunction "1_1") (pintype "passive"))
      (node (ref "C11") (pin "1") (pinfunction "1_1") (pintype "passive"))
      (node (ref "C12") (pin "1") (pinfunction "1_1") (pintype "passive"))
      (node (ref "C13") (pin "1") (pinfunction "1_1") (pintype "passive"))
      (node (ref "C14") (pin "2") (pinfunction "2_2") (pintype "passive"))
      (node (ref "C15") (pin "1") (pinfunction "1_1") (pintype "passive"))
      (node (ref "C16") (pin "1") (pinfunction "1_1") (pintype "passive"))
      (node (ref "C17") (pin "-") (pinfunction "-_-") (pintype "passive"))
      (node (ref "C18") (pin "2") (pinfunction "2_2") (pintype "passive"))
      (node (ref "C19") (pin "1") (pinfunction "1_1") (pintype "passive"))
      (node (ref "C2") (pin "1") (pinfunction "1_1") (pintype "passive"))
      (node (ref "C20") (pin "2") (pinfunction "2_2") (pintype "passive"))
      (node (ref "C21") (pin "2") (pinfunction "2_2") (pintype "passive"))
      (node (ref "C22") (pin "2") (pinfunction "2_2") (pintype "passive"))
      (node (ref "C23") (pin "2") (pinfunction "2_2") (pintype "passive"))
      (node (ref "C24") (pin "1") (pinfunction "1_1") (pintype "passive"))
      (node (ref "C25") (pin "2") (pinfunction "2_2") (pintype "passive"))
      (node (ref "C26") (pin "1") (pinfunction "1_1") (pintype "passive"))
      (node (ref "C27") (pin "1") (pinfunction "1_1") (pintype "passive"))
      (node (ref "C28") (pin "1") (pinfunction "1_1") (pintype "passive"))
      (node (ref "C3") (pin "1") (pinfunction "1_1") (pintype "passive"))
      (node (ref "C4") (pin "1") (pinfunction "1_1") (pintype "passive"))
      (node (ref "C5") (pin "-") (pinfunction "-_-") (pintype "passive"))
      (node (ref "C6") (pin "1") (pinfunction "1_1") (pintype "passive"))
      (node (ref "C7") (pin "1") (pinfunction "1_1") (pintype "passive"))
      (node (ref "C8") (pin "1") (pinfunction "1_1") (pintype "passive"))
      (node (ref "C9") (pin "1") (pinfunction "1_1") (pintype "passive"))
      (node (ref "J1") (pin "2") (pinfunction "PIN_2") (pintype "bidirectional"))
      (node (ref "J1") (pin "4") (pinfunction "PIN_4") (pintype "bidirectional"))
      (node (ref "J1") (pin "6") (pinfunction "PIN_6") (pintype "bidirectional"))
      (node (ref "J2") (pin "4") (pinfunction "4_4") (pintype "passive"))
      (node (ref "J3") (pin "GND") (pinfunction "GND_GND") (pintype "bidirectional"))
      (node (ref "J3") (pin "GNDBREAK") (pinfunction "GNDBREAK_GNDBREAK") (pintype "bidirectional"))
      (node (ref "J4") (pin "3") (pinfunction "3_3") (pintype "passive"))
      (node (ref "J4") (pin "5") (pinfunction "5_5") (pintype "passive"))
      (node (ref "J4") (pin "7") (pinfunction "7_7") (pintype "passive"))
      (node (ref "J4") (pin "8") (pinfunction "8_8") (pintype "passive"))
      (node (ref "J5") (pin "3") (pinfunction "3_3") (pintype "passive"))
      (node (ref "J5") (pin "5") (pinfunction "5_5") (pintype "passive"))
      (node (ref "J5") (pin "7") (pinfunction "7_7") (pintype "passive"))
      (node (ref "J5") (pin "8") (pinfunction "8_8") (pintype "passive"))
      (node (ref "J6") (pin "3") (pinfunction "3_3") (pintype "passive"))
      (node (ref "J6") (pin "5") (pinfunction "5_5") (pintype "passive"))
      (node (ref "J6") (pin "7") (pinfunction "7_7") (pintype "passive"))
      (node (ref "J6") (pin "8") (pinfunction "8_8") (pintype "passive"))
      (node (ref "J7") (pin "GND") (pinfunction "GND_GND") (pintype "bidirectional"))
      (node (ref "JP4") (pin "3") (pinfunction "3_3") (pintype "passive"))
      (node (ref "JP5") (pin "2") (pinfunction "2_2") (pintype "passive"))
      (node (ref "LED1") (pin "C") (pinfunction "C_C") (pintype "passive"))
      (node (ref "R17") (pin "2") (pinfunction "2_2") (pintype "passive"))
      (node (ref "R19") (pin "2") (pinfunction "2_2") (pintype "passive"))
      (node (ref "R23") (pin "2") (pinfunction "2_2") (pintype "passive"))
      (node (ref "R24") (pin "2") (pinfunction "2_2") (pintype "passive"))
      (node (ref "R37") (pin "2") (pinfunction "2_2") (pintype "passive"))
      (node (ref "R39") (pin "1") (pinfunction "1_1") (pintype "passive"))
      (node (ref "R43") (pin "1") (pinfunction "1_1") (pintype "passive"))
      (node (ref "R44") (pin "1") (pinfunction "1_1") (pintype "passive"))
      (node (ref "R45") (pin "1") (pinfunction "1_1") (pintype "passive"))
      (node (ref "SV1") (pin "1") (pinfunction "1_1") (pintype "passive"))
      (node (ref "SV2") (pin "1") (pinfunction "1_1") (pintype "passive"))
      (node (ref "SV3") (pin "1") (pinfunction "1_1") (pintype "passive"))
      (node (ref "T1") (pin "E") (pinfunction "E_E") (pintype "passive"))
      (node (ref "T2") (pin "E") (pinfunction "E_E") (pintype "passive"))
      (node (ref "T4") (pin "2") (pinfunction "S_2") (pintype "passive"))
      (node (ref "U1") (pin "4") (pinfunction "GND_4") (pintype "bidirectional"))
      (node (ref "U2") (pin "4") (pinfunction "GND_4") (pintype "bidirectional"))
      (node (ref "U3") (pin "4") (pinfunction "GND_4") (pintype "bidirectional"))
      (node (ref "U4") (pin "5") (pinfunction "GND_5") (pintype "bidirectional"))
      (node (ref "U4") (pin "6") (pinfunction "GND_6") (pintype "bidirectional"))
      (node (ref "U4") (pin "7") (pinfunction "GND_7") (pintype "bidirectional"))
      (node (ref "U4") (pin "8") (pinfunction "GND_8") (pintype "bidirectional"))
      (node (ref "U5") (pin "15") (pinfunction "PGND_15") (pintype "bidirectional"))
      (node (ref "U5") (pin "16") (pinfunction "PGND_16") (pintype "bidirectional"))
      (node (ref "U5") (pin "5") (pinfunction "FB_5") (pintype "bidirectional"))
      (node (ref "U5") (pin "6") (pinfunction "AGND_6") (pintype "bidirectional"))
      (node (ref "U5") (pin "7") (pinfunction "FSW_7") (pintype "bidirectional"))
      (node (ref "U5") (pin "8") (pinfunction "DEF_8") (pintype "bidirectional"))
      (node (ref "U5") (pin "EXT") (pinfunction "EXT_EXT") (pintype "bidirectional"))
      (node (ref "U6") (pin "2") (pinfunction "GND_2") (pintype "bidirectional"))
      (node (ref "U7") (pin "20") (pinfunction "AVSS_20") (pintype "power_in"))
      (node (ref "U7") (pin "25") (pinfunction "VSS_25") (pintype "power_in"))
      (node (ref "U7") (pin "41") (pinfunction "VSS_41") (pintype "power_in"))
      (node (ref "U7") (pin "9") (pinfunction "VSS_9") (pintype "power_in"))
      (node (ref "U8") (pin "1") (pinfunction "GND_1") (pintype "power_in"))
    )
    (net (code "68") (name "Net-(C5-Pad+)") (class "Default")
      (node (ref "C5") (pin "+") (pinfunction "+_+") (pintype "passive"))
      (node (ref "D1") (pin "C") (pinfunction "C_C") (pintype "passive"))
      (node (ref "F2") (pin "1") (pinfunction "1_1") (pintype "passive"))
    )
    (net (code "69") (name "Net-(C6-Pad2)") (class "Default")
      (node (ref "C6") (pin "2") (pinfunction "2_2") (pintype "passive"))
      (node (ref "J2") (pin "5") (pinfunction "5_5") (pintype "passive"))
      (node (ref "R1") (pin "1") (pinfunction "1_1") (pintype "passive"))
      (node (ref "R12") (pin "2") (pinfunction "2_2") (pintype "passive"))
    )
    (net (code "70") (name "Net-(C7-Pad2)") (class "Default")
      (node (ref "C7") (pin "2") (pinfunction "2_2") (pintype "passive"))
      (node (ref "J2") (pin "3") (pinfunction "3_3") (pintype "passive"))
      (node (ref "R5") (pin "2") (pinfunction "2_2") (pintype "passive"))
    )
    (net (code "71") (name "Net-(D2-PadA)") (class "Default")
      (node (ref "D2") (pin "A") (pinfunction "A_A") (pintype "passive"))
      (node (ref "K1") (pin "5") (pinfunction "5_5") (pintype "passive"))
      (node (ref "T1") (pin "C") (pinfunction "C_C") (pintype "passive"))
    )
    (net (code "72") (name "Net-(D4-PadA)") (class "Default")
      (node (ref "D4") (pin "A") (pinfunction "A_A") (pintype "passive"))
      (node (ref "K2") (pin "5") (pinfunction "5_5") (pintype "passive"))
      (node (ref "T2") (pin "C") (pinfunction "C_C") (pintype "passive"))
    )
    (net (code "73") (name "Net-(D5-PadC)") (class "Default")
      (node (ref "D5") (pin "C") (pinfunction "C_C") (pintype "passive"))
      (node (ref "D6") (pin "A") (pinfunction "A_A") (pintype "passive"))
    )
    (net (code "74") (name "Net-(D6-PadC)") (class "Default")
      (node (ref "D6") (pin "C") (pinfunction "C_C") (pintype "passive"))
      (node (ref "J2") (pin "2") (pinfunction "2_2") (pintype "passive"))
      (node (ref "Q1") (pin "B") (pinfunction "B_B") (pintype "passive"))
    )
    (net (code "75") (name "Net-(J1A-PIN)") (class "Default")
      (node (ref "D1") (pin "A") (pinfunction "A_A") (pintype "passive"))
      (node (ref "F1") (pin "1") (pinfunction "1_1") (pintype "passive"))
      (node (ref "J1") (pin "1") (pinfunction "PIN_1") (pintype "bidirectional"))
      (node (ref "J3") (pin "PWR") (pinfunction "PWR_PWR") (pintype "bidirectional"))
    )
    (net (code "76") (name "Net-(J1C-PIN)") (class "Default")
      (node (ref "J1") (pin "3") (pinfunction "PIN_3") (pintype "bidirectional"))
      (node (ref "K1") (pin "7") (pinfunction "S_7") (pintype "passive"))
    )
    (net (code "77") (name "Net-(J1E-PIN)") (class "Default")
      (node (ref "J1") (pin "5") (pinfunction "PIN_5") (pintype "bidirectional"))
      (node (ref "K2") (pin "1") (pinfunction "P_1") (pintype "passive"))
    )
    (net (code "78") (name "Net-(L1-1)") (class "Default")
      (node (ref "L1") (pin "P$1") (pinfunction "1_P$1") (pintype "passive"))
      (node (ref "U5") (pin "1") (pinfunction "SW_1") (pintype "bidirectional"))
      (node (ref "U5") (pin "2") (pinfunction "SW_2") (pintype "bidirectional"))
      (node (ref "U5") (pin "3") (pinfunction "SW_3") (pintype "bidirectional"))
    )
    (net (code "79") (name "Net-(LED1-PadA)") (class "Default")
      (node (ref "LED1") (pin "A") (pinfunction "A_A") (pintype "passive"))
      (node (ref "R25") (pin "2") (pinfunction "2_2") (pintype "passive"))
    )
    (net (code "80") (name "Net-(LED2-PadA)") (class "Default")
      (node (ref "LED2") (pin "A") (pinfunction "A_A") (pintype "passive"))
      (node (ref "R38") (pin "2") (pinfunction "2_2") (pintype "passive"))
    )
    (net (code "81") (name "Net-(R18-Pad2)") (class "Default")
      (node (ref "R18") (pin "2") (pinfunction "2_2") (pintype "passive"))
      (node (ref "R19") (pin "1") (pinfunction "1_1") (pintype "passive"))
      (node (ref "T1") (pin "B") (pinfunction "B_B") (pintype "passive"))
    )
    (net (code "82") (name "Net-(R22-Pad2)") (class "Default")
      (node (ref "R22") (pin "2") (pinfunction "2_2") (pintype "passive"))
      (node (ref "R24") (pin "1") (pinfunction "1_1") (pintype "passive"))
      (node (ref "T2") (pin "B") (pinfunction "B_B") (pintype "passive"))
    )
    (net (code "83") (name "Net-(T3-D)") (class "Default")
      (node (ref "D3") (pin "A") (pinfunction "A_A") (pintype "passive"))
      (node (ref "F3") (pin "2") (pinfunction "2_2") (pintype "bidirectional"))
      (node (ref "T3") (pin "3") (pinfunction "D_3") (pintype "passive"))
    )
    (net (code "84") (name "Net-(T3-G)") (class "Default")
      (node (ref "R20") (pin "2") (pinfunction "2_2") (pintype "passive"))
      (node (ref "R21") (pin "1") (pinfunction "1_1") (pintype "passive"))
      (node (ref "T3") (pin "1") (pinfunction "G_1") (pintype "passive"))
    )
    (net (code "85") (name "Net-(T4-D)") (class "Default")
      (node (ref "R21") (pin "2") (pinfunction "2_2") (pintype "passive"))
      (node (ref "T4") (pin "3") (pinfunction "D_3") (pintype "passive"))
    )
    (net (code "86") (name "Net-(U5-SS_TR)") (class "Default")
      (node (ref "C12") (pin "2") (pinfunction "2_2") (pintype "passive"))
      (node (ref "U5") (pin "9") (pinfunction "SS_TR_9") (pintype "bidirectional"))
    )
    (net (code "87") (name "Net-(U6-VCORE)") (class "Default")
      (node (ref "C14") (pin "1") (pinfunction "1_1") (pintype "passive"))
      (node (ref "U6") (pin "1") (pinfunction "VCORE_1") (pintype "bidirectional"))
    )
    (net (code "88") (name "Net-(U7-AVDD)") (class "Default")
      (node (ref "C20") (pin "1") (pinfunction "1_1") (pintype "passive"))
      (node (ref "L2") (pin "1") (pinfunction "1_1") (pintype "passive"))
      (node (ref "U7") (pin "19") (pinfunction "AVDD_19") (pintype "power_in"))
    )
    (net (code "89") (name "Net-(U7-VCAP)") (class "Default")
      (node (ref "C24") (pin "2") (pinfunction "2_2") (pintype "passive"))
      (node (ref "U7") (pin "56") (pinfunction "VCAP_56") (pintype "power_in"))
    )
    (net (code "90") (name "Net-(U7-~{MCLR})") (class "Default")
      (node (ref "R36") (pin "2") (pinfunction "2_2") (pintype "passive"))
      (node (ref "U7") (pin "7") (pinfunction "~{MCLR}_7") (pintype "input"))
    )
    (net (code "91") (name "Net-(U8-CON)") (class "Default")
      (node (ref "C19") (pin "2") (pinfunction "2_2") (pintype "passive"))
      (node (ref "U8") (pin "5") (pinfunction "CON_5") (pintype "input"))
    )
    (net (code "92") (name "Net-(U8-DIS)") (class "Default")
      (node (ref "R27") (pin "1") (pinfunction "1_1") (pintype "passive"))
      (node (ref "R28") (pin "2") (pinfunction "2_2") (pintype "passive"))
      (node (ref "U8") (pin "7") (pinfunction "DIS_7") (pintype "input"))
    )
    (net (code "93") (name "Net-(U8-OUT)") (class "Default")
      (node (ref "JP3") (pin "1") (pinfunction "1_1") (pintype "passive"))
      (node (ref "U8") (pin "3") (pinfunction "OUT_3") (pintype "output"))
    )
    (net (code "94") (name "Net-(U8-TRE)") (class "Default")
      (node (ref "C17") (pin "+") (pinfunction "+_+") (pintype "passive"))
      (node (ref "R26") (pin "1") (pinfunction "1_1") (pintype "passive"))
      (node (ref "R27") (pin "2") (pinfunction "2_2") (pintype "passive"))
      (node (ref "U8") (pin "2") (pinfunction "TRI_2") (pintype "input"))
      (node (ref "U8") (pin "6") (pinfunction "TRE_6") (pintype "input"))
    )
    (net (code "95") (name "V+") (class "Default")
      (node (ref "F1") (pin "2") (pinfunction "2_2") (pintype "passive"))
      (node (ref "K1") (pin "1") (pinfunction "P_1") (pintype "passive"))
      (node (ref "K2") (pin "7") (pinfunction "S_7") (pintype "passive"))
    )
    (net (code "96") (name "unconnected-(J2-Pad1)") (class "Default")
      (node (ref "J2") (pin "1") (pinfunction "1_1") (pintype "passive"))
    )
    (net (code "97") (name "unconnected-(J2-Pad6)") (class "Default")
      (node (ref "J2") (pin "6") (pinfunction "6_6") (pintype "passive"))
    )
    (net (code "98") (name "unconnected-(U4-FLAG-Pad4)") (class "Default")
      (node (ref "U4") (pin "4") (pinfunction "FLAG_4") (pintype "bidirectional"))
    )
    (net (code "99") (name "unconnected-(U5-PG-Pad4)") (class "Default")
      (node (ref "U5") (pin "4") (pinfunction "PG_4") (pintype "bidirectional"))
    )
    (net (code "100") (name "unconnected-(U6-ALARM-Pad4)") (class "Default")
      (node (ref "U6") (pin "4") (pinfunction "ALARM_4") (pintype "bidirectional"))
    )
    (net (code "101") (name "unconnected-(U6-PDM_H-Pad6)") (class "Default")
      (node (ref "U6") (pin "6") (pinfunction "PDM_H_6") (pintype "bidirectional"))
    )
    (net (code "102") (name "unconnected-(U6-PDM_T-Pad5)") (class "Default")
      (node (ref "U6") (pin "5") (pinfunction "PDM_T_5") (pintype "bidirectional"))
    )
  )
)
